# Amplifier.net
KiCad netlist of a schematic drawn in EAGLE
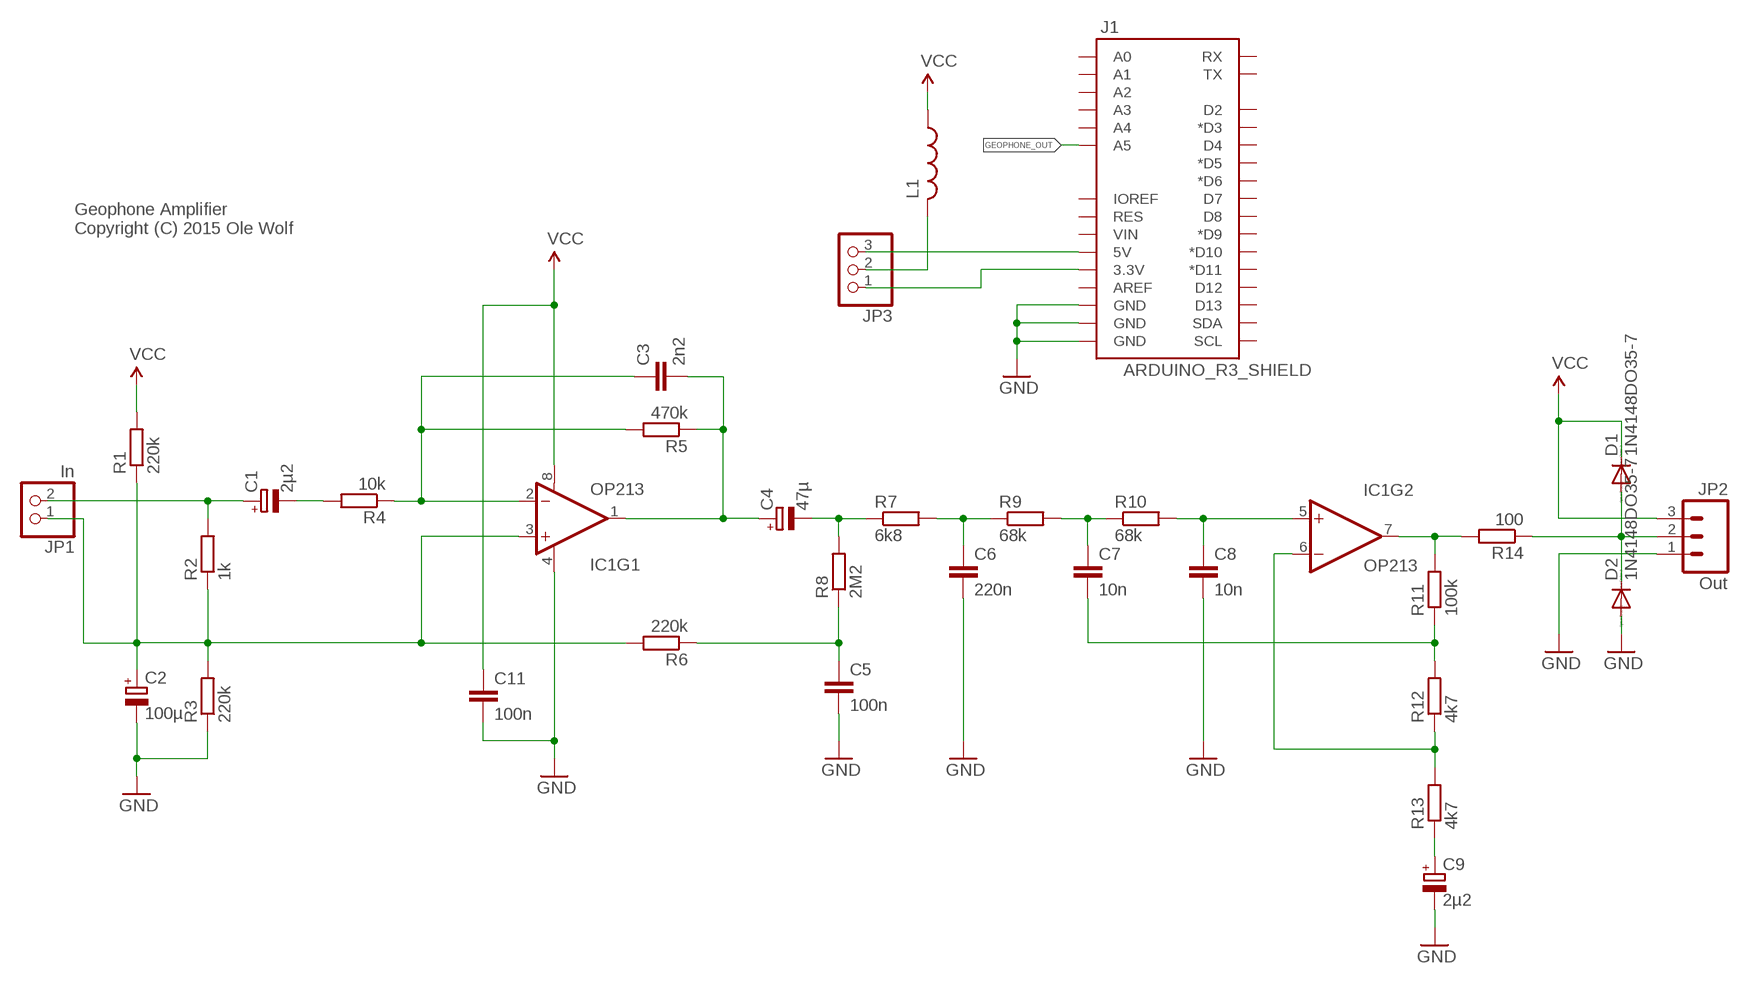
[diagram p0: schematic, sheet 1]

(export (version "E")
  (design (tool "Eeschema 10.0.6"))
  (components
    (comp (ref "C1")
      (value "2µ2")
      (footprint "eagle-import:E2-5")
      (libsource (lib "eagle-import") (part "CPOL-EUE2-5"))
    )
    (comp (ref "C2")
      (value "100µ")
      (footprint "eagle-import:E2-5")
      (libsource (lib "eagle-import") (part "CPOL-EUE2-5"))
    )
    (comp (ref "C3")
      (value "2n2")
      (footprint "eagle-import:C025-025X050")
      (libsource (lib "eagle-import") (part "C-EU025-025X050"))
    )
    (comp (ref "C4")
      (value "47µ")
      (footprint "eagle-import:E2-5")
      (libsource (lib "eagle-import") (part "CPOL-EUE2-5"))
    )
    (comp (ref "C5")
      (value "100n")
      (footprint "eagle-import:C025-025X050")
      (libsource (lib "eagle-import") (part "C-EU025-025X050"))
    )
    (comp (ref "C6")
      (value "220n")
      (footprint "eagle-import:C025-025X050")
      (libsource (lib "eagle-import") (part "C-EU025-025X050"))
    )
    (comp (ref "C7")
      (value "10n")
      (footprint "eagle-import:C025-025X050")
      (libsource (lib "eagle-import") (part "C-EU025-025X050"))
    )
    (comp (ref "C8")
      (value "10n")
      (footprint "eagle-import:C025-025X050")
      (libsource (lib "eagle-import") (part "C-EU025-025X050"))
    )
    (comp (ref "C9")
      (value "2µ2")
      (footprint "eagle-import:E2-5")
      (libsource (lib "eagle-import") (part "CPOL-EUE2-5"))
    )
    (comp (ref "C11")
      (value "100n")
      (footprint "eagle-import:C025-025X050")
      (libsource (lib "eagle-import") (part "C-EU025-025X050"))
    )
    (comp (ref "D1")
      (value "1N4148DO35-7")
      (footprint "eagle-import:DO35-7")
      (libsource (lib "eagle-import") (part "1N4148DO35-7"))
    )
    (comp (ref "D2")
      (value "1N4148DO35-7")
      (footprint "eagle-import:DO35-7")
      (libsource (lib "eagle-import") (part "1N4148DO35-7"))
    )
    (comp (ref "IC1")
      (value "OP213")
      (footprint "eagle-import:DIP08")
      (libsource (lib "eagle-import") (part "LM358"))
    )
    (comp (ref "J1")
      (value "ARDUINO_R3_SHIELD")
      (footprint "eagle-import:UNO_R3_SHIELD")
      (libsource (lib "eagle-import") (part "ARDUINO_R3_SHIELD"))
    )
    (comp (ref "JP1")
      (value "In")
      (footprint "eagle-import:1X02")
      (libsource (lib "eagle-import") (part "PINHD-1X2"))
    )
    (comp (ref "JP2")
      (value "Out")
      (footprint "eagle-import:1X03_LONGPADS")
      (libsource (lib "eagle-import") (part "M03LONGPADS"))
    )
    (comp (ref "JP3")
      (value "PINHD-1X3")
      (footprint "eagle-import:1X03")
      (libsource (lib "eagle-import") (part "PINHD-1X3"))
    )
    (comp (ref "L1")
      (value "L-US0207/2V")
      (footprint "eagle-import:0207_2V")
      (libsource (lib "eagle-import") (part "L-US0207/2V"))
    )
    (comp (ref "R1")
      (value "220k")
      (footprint "eagle-import:0207_12")
      (libsource (lib "eagle-import") (part "R-EU_0207/12"))
    )
    (comp (ref "R2")
      (value "1k")
      (footprint "eagle-import:0207_12")
      (libsource (lib "eagle-import") (part "R-EU_0207/12"))
    )
    (comp (ref "R3")
      (value "220k")
      (footprint "eagle-import:0207_12")
      (libsource (lib "eagle-import") (part "R-EU_0207/12"))
    )
    (comp (ref "R4")
      (value "10k")
      (footprint "eagle-import:0207_12")
      (libsource (lib "eagle-import") (part "R-EU_0207/12"))
    )
    (comp (ref "R5")
      (value "470k")
      (footprint "eagle-import:0207_12")
      (libsource (lib "eagle-import") (part "R-EU_0207/12"))
    )
    (comp (ref "R6")
      (value "220k")
      (footprint "eagle-import:0207_12")
      (libsource (lib "eagle-import") (part "R-EU_0207/12"))
    )
    (comp (ref "R7")
      (value "6k8")
      (footprint "eagle-import:0207_12")
      (libsource (lib "eagle-import") (part "R-EU_0207/12"))
    )
    (comp (ref "R8")
      (value "2M2")
      (footprint "eagle-import:0207_12")
      (libsource (lib "eagle-import") (part "R-EU_0207/12"))
    )
    (comp (ref "R9")
      (value "68k")
      (footprint "eagle-import:0207_12")
      (libsource (lib "eagle-import") (part "R-EU_0207/12"))
    )
    (comp (ref "R10")
      (value "68k")
      (footprint "eagle-import:0207_12")
      (libsource (lib "eagle-import") (part "R-EU_0207/12"))
    )
    (comp (ref "R11")
      (value "100k")
      (footprint "eagle-import:0207_12")
      (libsource (lib "eagle-import") (part "R-EU_0207/12"))
    )
    (comp (ref "R12")
      (value "4k7")
      (footprint "eagle-import:0207_12")
      (libsource (lib "eagle-import") (part "R-EU_0207/12"))
    )
    (comp (ref "R13")
      (value "4k7")
      (footprint "eagle-import:0207_12")
      (libsource (lib "eagle-import") (part "R-EU_0207/12"))
    )
    (comp (ref "R14")
      (value "100")
      (footprint "eagle-import:0207_12")
      (libsource (lib "eagle-import") (part "R-EU_0207/12"))
    )
  )
  (nets
    (net (code "1") (name "GEOPHONE_OUT") (class "Default")
      (node (ref "D1") (pin "A") (pinfunction "A_A") (pintype "passive"))
      (node (ref "D2") (pin "C") (pinfunction "C_C") (pintype "passive"))
      (node (ref "J1") (pin "A5") (pinfunction "A5_A5") (pintype "bidirectional"))
      (node (ref "JP2") (pin "2") (pinfunction "2_2") (pintype "passive"))
      (node (ref "R14") (pin "1") (pinfunction "1_1") (pintype "passive"))
    )
    (net (code "2") (name "GND") (class "Default")
      (node (ref "C11") (pin "2") (pinfunction "2_2") (pintype "passive"))
      (node (ref "C2") (pin "-") (pinfunction "-_-") (pintype "passive"))
      (node (ref "C5") (pin "2") (pinfunction "2_2") (pintype "passive"))
      (node (ref "C6") (pin "2") (pinfunction "2_2") (pintype "passive"))
      (node (ref "C8") (pin "2") (pinfunction "2_2") (pintype "passive"))
      (node (ref "C9") (pin "-") (pinfunction "-_-") (pintype "passive"))
      (node (ref "D2") (pin "A") (pinfunction "A_A") (pintype "passive"))
      (node (ref "IC1") (pin "4") (pinfunction "V-_4") (pintype "power_in"))
      (node (ref "J1") (pin "GND@0") (pinfunction "GND_GND@0") (pintype "bidirectional"))
      (node (ref "J1") (pin "GND@1") (pinfunction "GND_GND@1") (pintype "bidirectional"))
      (node (ref "J1") (pin "GND@2") (pinfunction "GND_GND@2") (pintype "bidirectional"))
      (node (ref "JP2") (pin "1") (pinfunction "1_1") (pintype "passive"))
      (node (ref "R3") (pin "1") (pinfunction "1_1") (pintype "passive"))
    )
    (net (code "3") (name "Net-(C1-Pad+)") (class "Default")
      (node (ref "C1") (pin "+") (pinfunction "+_+") (pintype "passive"))
      (node (ref "JP1") (pin "2") (pinfunction "2_2") (pintype "passive"))
      (node (ref "R2") (pin "2") (pinfunction "2_2") (pintype "passive"))
    )
    (net (code "4") (name "Net-(C1-Pad-)") (class "Default")
      (node (ref "C1") (pin "-") (pinfunction "-_-") (pintype "passive"))
      (node (ref "R4") (pin "2") (pinfunction "2_2") (pintype "passive"))
    )
    (net (code "5") (name "Net-(C4-Pad-)") (class "Default")
      (node (ref "C4") (pin "-") (pinfunction "-_-") (pintype "passive"))
      (node (ref "R7") (pin "1") (pinfunction "1_1") (pintype "passive"))
      (node (ref "R8") (pin "2") (pinfunction "2_2") (pintype "passive"))
    )
    (net (code "6") (name "Net-(C5-Pad1)") (class "Default")
      (node (ref "C5") (pin "1") (pinfunction "1_1") (pintype "passive"))
      (node (ref "R6") (pin "1") (pinfunction "1_1") (pintype "passive"))
      (node (ref "R8") (pin "1") (pinfunction "1_1") (pintype "passive"))
    )
    (net (code "7") (name "Net-(C6-Pad1)") (class "Default")
      (node (ref "C6") (pin "1") (pinfunction "1_1") (pintype "passive"))
      (node (ref "R7") (pin "2") (pinfunction "2_2") (pintype "passive"))
      (node (ref "R9") (pin "1") (pinfunction "1_1") (pintype "passive"))
    )
    (net (code "8") (name "Net-(C7-Pad1)") (class "Default")
      (node (ref "C7") (pin "1") (pinfunction "1_1") (pintype "passive"))
      (node (ref "R10") (pin "1") (pinfunction "1_1") (pintype "passive"))
      (node (ref "R9") (pin "2") (pinfunction "2_2") (pintype "passive"))
    )
    (net (code "9") (name "Net-(C7-Pad2)") (class "Default")
      (node (ref "C7") (pin "2") (pinfunction "2_2") (pintype "passive"))
      (node (ref "R11") (pin "1") (pinfunction "1_1") (pintype "passive"))
      (node (ref "R12") (pin "2") (pinfunction "2_2") (pintype "passive"))
    )
    (net (code "10") (name "Net-(C9-Pad+)") (class "Default")
      (node (ref "C9") (pin "+") (pinfunction "+_+") (pintype "passive"))
      (node (ref "R13") (pin "1") (pinfunction "1_1") (pintype "passive"))
    )
    (net (code "11") (name "Net-(IC1A-+IN)") (class "Default")
      (node (ref "C2") (pin "+") (pinfunction "+_+") (pintype "passive"))
      (node (ref "IC1") (pin "3") (pinfunction "+IN_3") (pintype "input"))
      (node (ref "JP1") (pin "1") (pinfunction "1_1") (pintype "passive"))
      (node (ref "R1") (pin "1") (pinfunction "1_1") (pintype "passive"))
      (node (ref "R2") (pin "1") (pinfunction "1_1") (pintype "passive"))
      (node (ref "R3") (pin "2") (pinfunction "2_2") (pintype "passive"))
      (node (ref "R6") (pin "2") (pinfunction "2_2") (pintype "passive"))
    )
    (net (code "12") (name "Net-(IC1A--IN)") (class "Default")
      (node (ref "C3") (pin "1") (pinfunction "1_1") (pintype "passive"))
      (node (ref "IC1") (pin "2") (pinfunction "-IN_2") (pintype "input"))
      (node (ref "R4") (pin "1") (pinfunction "1_1") (pintype "passive"))
      (node (ref "R5") (pin "2") (pinfunction "2_2") (pintype "passive"))
    )
    (net (code "13") (name "Net-(IC1A-OUT)") (class "Default")
      (node (ref "C3") (pin "2") (pinfunction "2_2") (pintype "passive"))
      (node (ref "C4") (pin "+") (pinfunction "+_+") (pintype "passive"))
      (node (ref "IC1") (pin "1") (pinfunction "OUT_1") (pintype "output"))
      (node (ref "R5") (pin "1") (pinfunction "1_1") (pintype "passive"))
    )
    (net (code "14") (name "Net-(IC1B-+IN)") (class "Default")
      (node (ref "C8") (pin "1") (pinfunction "1_1") (pintype "passive"))
      (node (ref "IC1") (pin "5") (pinfunction "+IN_5") (pintype "input"))
      (node (ref "R10") (pin "2") (pinfunction "2_2") (pintype "passive"))
    )
    (net (code "15") (name "Net-(IC1B--IN)") (class "Default")
      (node (ref "IC1") (pin "6") (pinfunction "-IN_6") (pintype "input"))
      (node (ref "R12") (pin "1") (pinfunction "1_1") (pintype "passive"))
      (node (ref "R13") (pin "2") (pinfunction "2_2") (pintype "passive"))
    )
    (net (code "16") (name "Net-(IC1B-OUT)") (class "Default")
      (node (ref "IC1") (pin "7") (pinfunction "OUT_7") (pintype "output"))
      (node (ref "R11") (pin "2") (pinfunction "2_2") (pintype "passive"))
      (node (ref "R14") (pin "2") (pinfunction "2_2") (pintype "passive"))
    )
    (net (code "17") (name "Net-(J1-Pad3.3V)") (class "Default")
      (node (ref "J1") (pin "3.3V") (pinfunction "3.3V_3.3V") (pintype "bidirectional"))
      (node (ref "JP3") (pin "1") (pinfunction "1_1") (pintype "passive"))
    )
    (net (code "18") (name "Net-(J1-Pad5V)") (class "Default")
      (node (ref "J1") (pin "5V") (pinfunction "5V_5V") (pintype "bidirectional"))
      (node (ref "JP3") (pin "3") (pinfunction "3_3") (pintype "passive"))
    )
    (net (code "19") (name "Net-(JP3-Pad2)") (class "Default")
      (node (ref "JP3") (pin "2") (pinfunction "2_2") (pintype "passive"))
      (node (ref "L1") (pin "2") (pinfunction "2_2") (pintype "passive"))
    )
    (net (code "20") (name "VCC") (class "Default")
      (node (ref "C11") (pin "1") (pinfunction "1_1") (pintype "passive"))
      (node (ref "D1") (pin "C") (pinfunction "C_C") (pintype "passive"))
      (node (ref "IC1") (pin "8") (pinfunction "V+_8") (pintype "power_in"))
      (node (ref "JP2") (pin "3") (pinfunction "3_3") (pintype "passive"))
      (node (ref "L1") (pin "1") (pinfunction "1_1") (pintype "passive"))
      (node (ref "R1") (pin "2") (pinfunction "2_2") (pintype "passive"))
    )
    (net (code "21") (name "unconnected-(J1-*D3-PadD3)") (class "Default")
      (node (ref "J1") (pin "D3") (pinfunction "*D3_D3") (pintype "bidirectional"))
    )
    (net (code "22") (name "unconnected-(J1-*D5-PadD5)") (class "Default")
      (node (ref "J1") (pin "D5") (pinfunction "*D5_D5") (pintype "bidirectional"))
    )
    (net (code "23") (name "unconnected-(J1-*D6-PadD6)") (class "Default")
      (node (ref "J1") (pin "D6") (pinfunction "*D6_D6") (pintype "bidirectional"))
    )
    (net (code "24") (name "unconnected-(J1-*D9-PadD9)") (class "Default")
      (node (ref "J1") (pin "D9") (pinfunction "*D9_D9") (pintype "bidirectional"))
    )
    (net (code "25") (name "unconnected-(J1-*D10-PadD10)") (class "Default")
      (node (ref "J1") (pin "D10") (pinfunction "*D10_D10") (pintype "bidirectional"))
    )
    (net (code "26") (name "unconnected-(J1-*D11-PadD11)") (class "Default")
      (node (ref "J1") (pin "D11") (pinfunction "*D11_D11") (pintype "bidirectional"))
    )
    (net (code "27") (name "unconnected-(J1-PadA0)") (class "Default")
      (node (ref "J1") (pin "A0") (pinfunction "A0_A0") (pintype "bidirectional"))
    )
    (net (code "28") (name "unconnected-(J1-PadA1)") (class "Default")
      (node (ref "J1") (pin "A1") (pinfunction "A1_A1") (pintype "bidirectional"))
    )
    (net (code "29") (name "unconnected-(J1-PadA2)") (class "Default")
      (node (ref "J1") (pin "A2") (pinfunction "A2_A2") (pintype "bidirectional"))
    )
    (net (code "30") (name "unconnected-(J1-PadA3)") (class "Default")
      (node (ref "J1") (pin "A3") (pinfunction "A3_A3") (pintype "bidirectional"))
    )
    (net (code "31") (name "unconnected-(J1-PadA4)") (class "Default")
      (node (ref "J1") (pin "A4") (pinfunction "A4_A4") (pintype "bidirectional"))
    )
    (net (code "32") (name "unconnected-(J1-PadAREF)") (class "Default")
      (node (ref "J1") (pin "AREF") (pinfunction "AREF_AREF") (pintype "bidirectional"))
    )
    (net (code "33") (name "unconnected-(J1-PadD2)") (class "Default")
      (node (ref "J1") (pin "D2") (pinfunction "D2_D2") (pintype "bidirectional"))
    )
    (net (code "34") (name "unconnected-(J1-PadD4)") (class "Default")
      (node (ref "J1") (pin "D4") (pinfunction "D4_D4") (pintype "bidirectional"))
    )
    (net (code "35") (name "unconnected-(J1-PadD7)") (class "Default")
      (node (ref "J1") (pin "D7") (pinfunction "D7_D7") (pintype "bidirectional"))
    )
    (net (code "36") (name "unconnected-(J1-PadD8)") (class "Default")
      (node (ref "J1") (pin "D8") (pinfunction "D8_D8") (pintype "bidirectional"))
    )
    (net (code "37") (name "unconnected-(J1-PadD12)") (class "Default")
      (node (ref "J1") (pin "D12") (pinfunction "D12_D12") (pintype "bidirectional"))
    )
    (net (code "38") (name "unconnected-(J1-PadD13)") (class "Default")
      (node (ref "J1") (pin "D13") (pinfunction "D13_D13") (pintype "bidirectional"))
    )
    (net (code "39") (name "unconnected-(J1-PadIOREF)") (class "Default")
      (node (ref "J1") (pin "IOREF") (pinfunction "IOREF_IOREF") (pintype "bidirectional"))
    )
    (net (code "40") (name "unconnected-(J1-PadRES)") (class "Default")
      (node (ref "J1") (pin "RES") (pinfunction "RES_RES") (pintype "bidirectional"))
    )
    (net (code "41") (name "unconnected-(J1-PadRX)") (class "Default")
      (node (ref "J1") (pin "RX") (pinfunction "RX_RX") (pintype "bidirectional"))
    )
    (net (code "42") (name "unconnected-(J1-PadSCL)") (class "Default")
      (node (ref "J1") (pin "SCL") (pinfunction "SCL_SCL") (pintype "bidirectional"))
    )
    (net (code "43") (name "unconnected-(J1-PadSDA)") (class "Default")
      (node (ref "J1") (pin "SDA") (pinfunction "SDA_SDA") (pintype "bidirectional"))
    )
    (net (code "44") (name "unconnected-(J1-PadTX)") (class "Default")
      (node (ref "J1") (pin "TX") (pinfunction "TX_TX") (pintype "bidirectional"))
    )
    (net (code "45") (name "unconnected-(J1-PadVIN)") (class "Default")
      (node (ref "J1") (pin "VIN") (pinfunction "VIN_VIN") (pintype "bidirectional"))
    )
  )
)
